# encorder.net
KiCad netlist of a schematic drawn in EAGLE
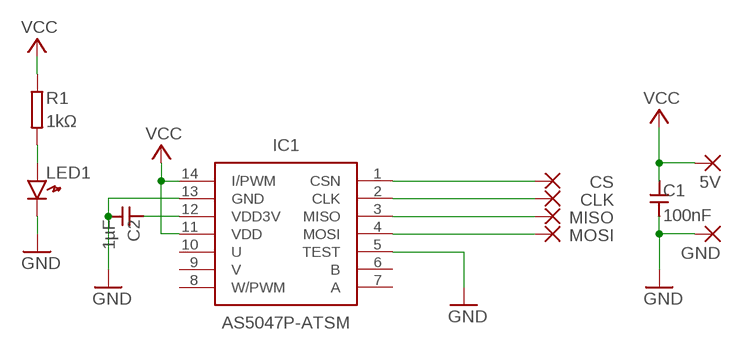
[diagram p0: schematic, sheet 1]

(export (version "E")
  (design (tool "Eeschema 10.0.6"))
  (components
    (comp (ref "5V")
      (value "SMD2")
      (footprint "eagle-import:SMD1,27-2,54")
      (libsource (lib "eagle-import") (part "SMD2"))
    )
    (comp (ref "C1")
      (value "100nF")
      (footprint "eagle-import:SMD1608")
      (libsource (lib "eagle-import") (part "CAPACITOR1608"))
    )
    (comp (ref "C2")
      (value "1µF")
      (footprint "eagle-import:SMD1608")
      (libsource (lib "eagle-import") (part "CAPACITOR1608"))
    )
    (comp (ref "CLK")
      (value "SMD2")
      (footprint "eagle-import:SMD1,27-2,54")
      (libsource (lib "eagle-import") (part "SMD2"))
    )
    (comp (ref "CS")
      (value "SMD2")
      (footprint "eagle-import:SMD1,27-2,54")
      (libsource (lib "eagle-import") (part "SMD2"))
    )
    (comp (ref "GND")
      (value "SMD2")
      (footprint "eagle-import:SMD1,27-2,54")
      (libsource (lib "eagle-import") (part "SMD2"))
    )
    (comp (ref "IC1")
      (value "AS5047P-ATSM")
      (footprint "eagle-import:SOP65P640X120-14N")
      (libsource (lib "eagle-import") (part "AS5047P-ATSM"))
    )
    (comp (ref "LED1")
      (value "LED1608")
      (footprint "eagle-import:LED1608")
      (libsource (lib "eagle-import") (part "LED1608"))
    )
    (comp (ref "MISO")
      (value "SMD2")
      (footprint "eagle-import:SMD1,27-2,54")
      (libsource (lib "eagle-import") (part "SMD2"))
    )
    (comp (ref "MOSI")
      (value "SMD2")
      (footprint "eagle-import:SMD1,27-2,54")
      (libsource (lib "eagle-import") (part "SMD2"))
    )
    (comp (ref "R1")
      (value "1kΩ")
      (footprint "eagle-import:SMD1608")
      (libsource (lib "eagle-import") (part "RESISTOR1608"))
    )
  )
  (nets
    (net (code "1") (name "GND") (class "Default")
      (node (ref "C1") (pin "2") (pinfunction "2_2") (pintype "passive"))
      (node (ref "C2") (pin "2") (pinfunction "2_2") (pintype "passive"))
      (node (ref "GND") (pin "1") (pinfunction "P_1") (pintype "passive"))
      (node (ref "IC1") (pin "13") (pinfunction "GND_13") (pintype "passive"))
      (node (ref "IC1") (pin "5") (pinfunction "TEST_5") (pintype "passive"))
      (node (ref "LED1") (pin "K") (pinfunction "K_K") (pintype "passive"))
    )
    (net (code "2") (name "Net-(CLK-P)") (class "Default")
      (node (ref "CLK") (pin "1") (pinfunction "P_1") (pintype "passive"))
      (node (ref "IC1") (pin "2") (pinfunction "CLK_2") (pintype "passive"))
    )
    (net (code "3") (name "Net-(CS-P)") (class "Default")
      (node (ref "CS") (pin "1") (pinfunction "P_1") (pintype "passive"))
      (node (ref "IC1") (pin "1") (pinfunction "CSN_1") (pintype "passive"))
    )
    (net (code "4") (name "Net-(IC1-MISO)") (class "Default")
      (node (ref "IC1") (pin "3") (pinfunction "MISO_3") (pintype "passive"))
      (node (ref "MISO") (pin "1") (pinfunction "P_1") (pintype "passive"))
    )
    (net (code "5") (name "Net-(IC1-MOSI)") (class "Default")
      (node (ref "IC1") (pin "4") (pinfunction "MOSI_4") (pintype "passive"))
      (node (ref "MOSI") (pin "1") (pinfunction "P_1") (pintype "passive"))
    )
    (net (code "6") (name "Net-(IC1-VDD3V)") (class "Default")
      (node (ref "C2") (pin "1") (pinfunction "1_1") (pintype "passive"))
      (node (ref "IC1") (pin "12") (pinfunction "VDD3V_12") (pintype "passive"))
    )
    (net (code "7") (name "Net-(LED1-PadA)") (class "Default")
      (node (ref "LED1") (pin "A") (pinfunction "A_A") (pintype "passive"))
      (node (ref "R1") (pin "2") (pinfunction "2_2") (pintype "passive"))
    )
    (net (code "8") (name "VCC") (class "Default")
      (node (ref "5V") (pin "1") (pinfunction "P_1") (pintype "passive"))
      (node (ref "C1") (pin "1") (pinfunction "1_1") (pintype "passive"))
      (node (ref "IC1") (pin "11") (pinfunction "VDD_11") (pintype "passive"))
      (node (ref "IC1") (pin "14") (pinfunction "I/PWM_14") (pintype "passive"))
      (node (ref "R1") (pin "1") (pinfunction "1_1") (pintype "passive"))
    )
    (net (code "9") (name "unconnected-(IC1-A-Pad7)") (class "Default")
      (node (ref "IC1") (pin "7") (pinfunction "A_7") (pintype "passive"))
    )
    (net (code "10") (name "unconnected-(IC1-B-Pad6)") (class "Default")
      (node (ref "IC1") (pin "6") (pinfunction "B_6") (pintype "passive"))
    )
    (net (code "11") (name "unconnected-(IC1-U-Pad10)") (class "Default")
      (node (ref "IC1") (pin "10") (pinfunction "U_10") (pintype "passive"))
    )
    (net (code "12") (name "unconnected-(IC1-V-Pad9)") (class "Default")
      (node (ref "IC1") (pin "9") (pinfunction "V_9") (pintype "passive"))
    )
    (net (code "13") (name "unconnected-(IC1-W{slash}PWM-Pad8)") (class "Default")
      (node (ref "IC1") (pin "8") (pinfunction "W/PWM_8") (pintype "passive"))
    )
  )
)
